# mini-usb-ftdi-breakout.net
KiCad netlist of a schematic drawn in EAGLE
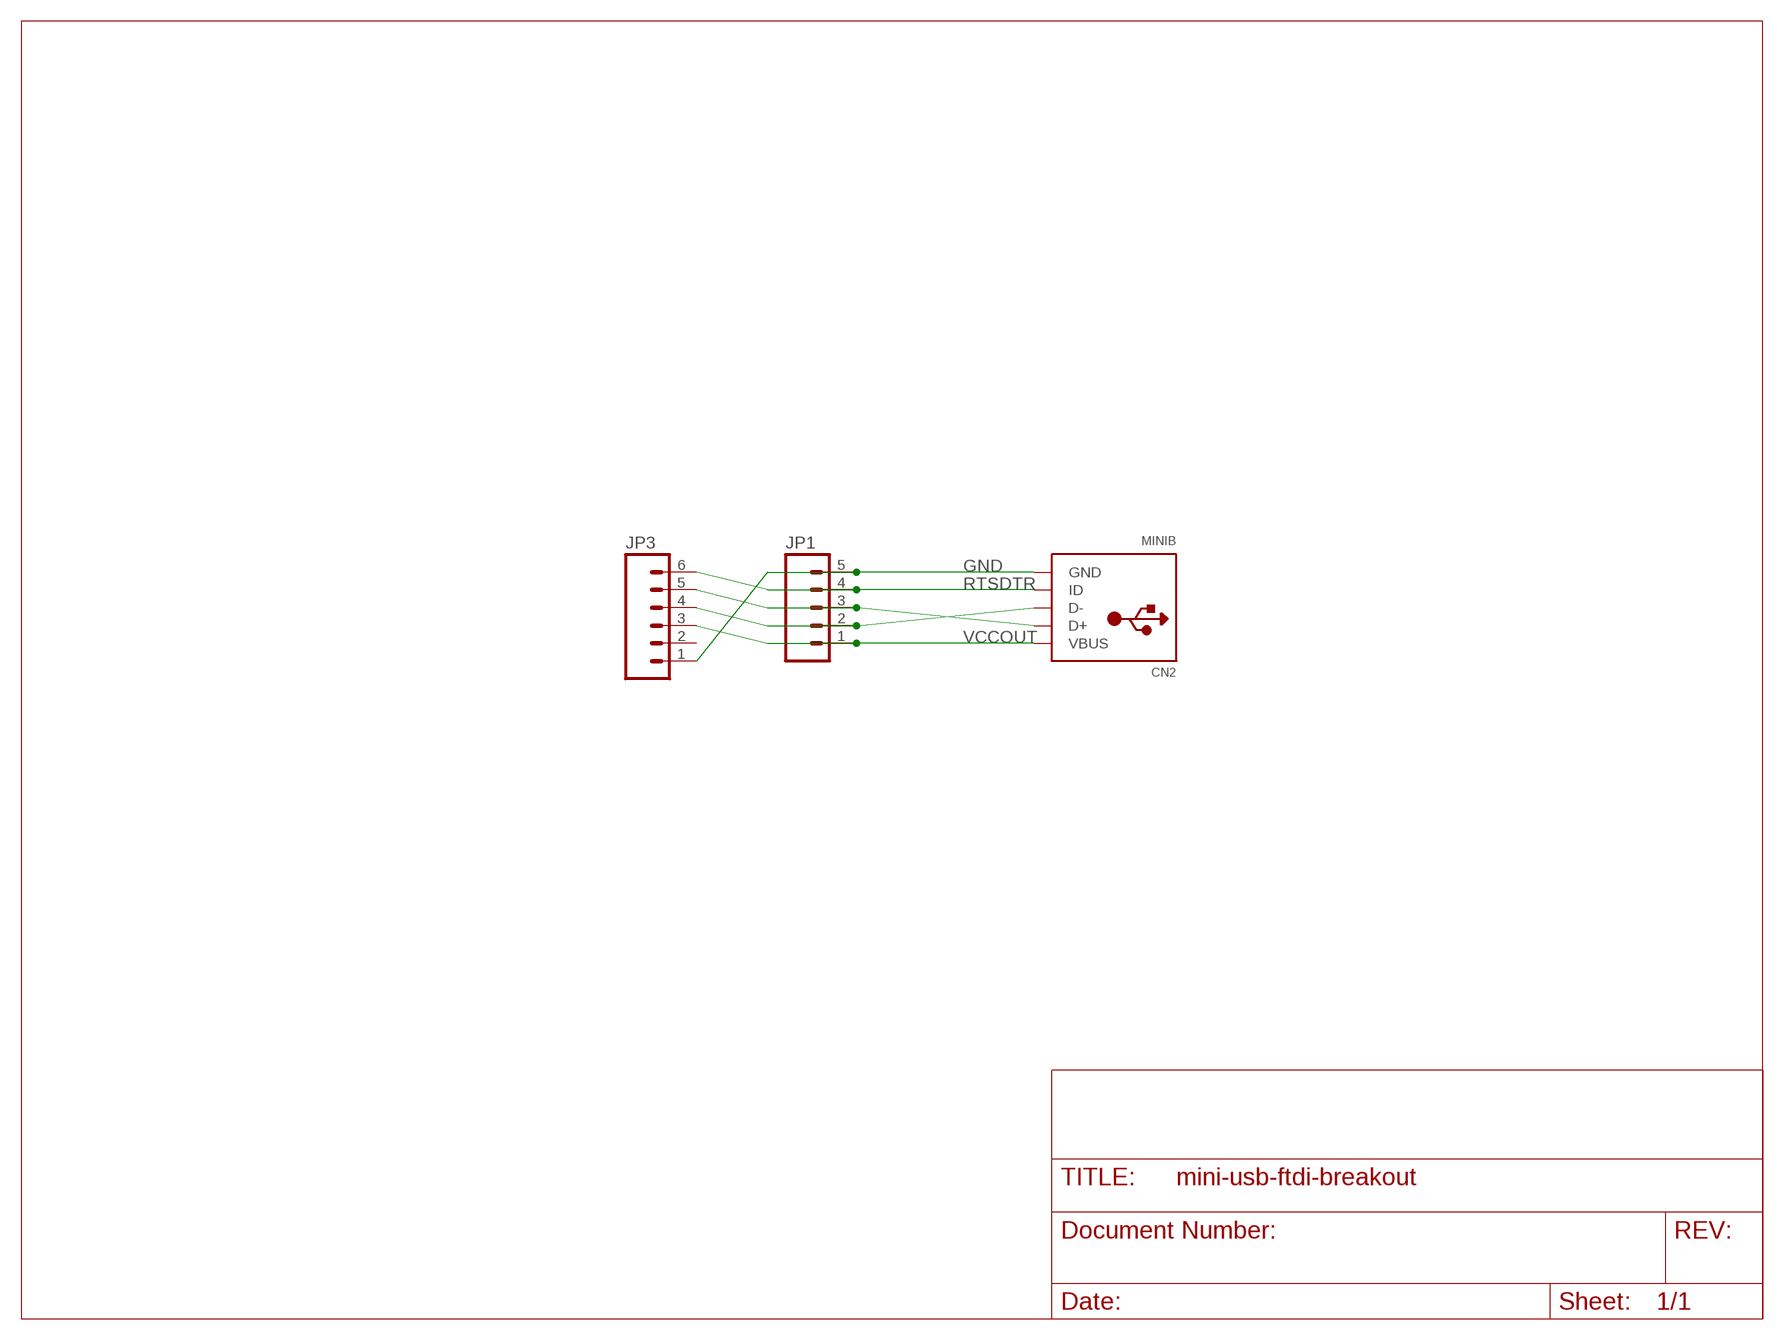
[diagram p0: schematic, sheet 1]

(export (version "E")
  (design (tool "Eeschema 10.0.6"))
  (components
    (comp (ref "CN2")
      (value "MINIB")
      (footprint "eagle-import:USB-MINIB")
      (libsource (lib "eagle-import") (part "USBMINIB"))
    )
    (comp (ref "JP1")
      (value "M05PTH")
      (footprint "eagle-import:1X05")
      (libsource (lib "eagle-import") (part "M05PTH"))
    )
    (comp (ref "JP3")
      (value "M06SMD")
      (footprint "eagle-import:1X06-SMD")
      (libsource (lib "eagle-import") (part "M06SMD"))
    )
  )
  (nets
    (net (code "1") (name "/GND") (class "Default")
      (node (ref "CN2") (pin "GND") (pinfunction "GND_GND") (pintype "power_in"))
      (node (ref "JP1") (pin "5") (pinfunction "5_5") (pintype "passive"))
      (node (ref "JP3") (pin "1") (pinfunction "1_1") (pintype "passive"))
    )
    (net (code "2") (name "/RTSDTR") (class "Default")
      (node (ref "CN2") (pin "ID") (pinfunction "ID_ID") (pintype "bidirectional"))
      (node (ref "JP1") (pin "4") (pinfunction "4_4") (pintype "passive"))
      (node (ref "JP3") (pin "6") (pinfunction "6_6") (pintype "passive"))
    )
    (net (code "3") (name "/VCCOUT") (class "Default")
      (node (ref "CN2") (pin "VBUS") (pinfunction "VBUS_VBUS") (pintype "power_in"))
      (node (ref "JP1") (pin "1") (pinfunction "1_1") (pintype "passive"))
      (node (ref "JP3") (pin "3") (pinfunction "3_3") (pintype "passive"))
    )
    (net (code "4") (name "Net-(CN2-PadD+)") (class "Default")
      (node (ref "CN2") (pin "D+") (pinfunction "D+_D+") (pintype "bidirectional"))
      (node (ref "JP1") (pin "3") (pinfunction "3_3") (pintype "passive"))
      (node (ref "JP3") (pin "5") (pinfunction "5_5") (pintype "passive"))
    )
    (net (code "5") (name "Net-(CN2-PadD-)") (class "Default")
      (node (ref "CN2") (pin "D-") (pinfunction "D-_D-") (pintype "bidirectional"))
      (node (ref "JP1") (pin "2") (pinfunction "2_2") (pintype "passive"))
      (node (ref "JP3") (pin "4") (pinfunction "4_4") (pintype "passive"))
    )
    (net (code "6") (name "unconnected-(JP3-Pad2)") (class "Default")
      (node (ref "JP3") (pin "2") (pinfunction "2_2") (pintype "passive"))
    )
  )
)
